# Buck_5V_line_07.net
KiCad netlist of a schematic drawn in Altium Designer
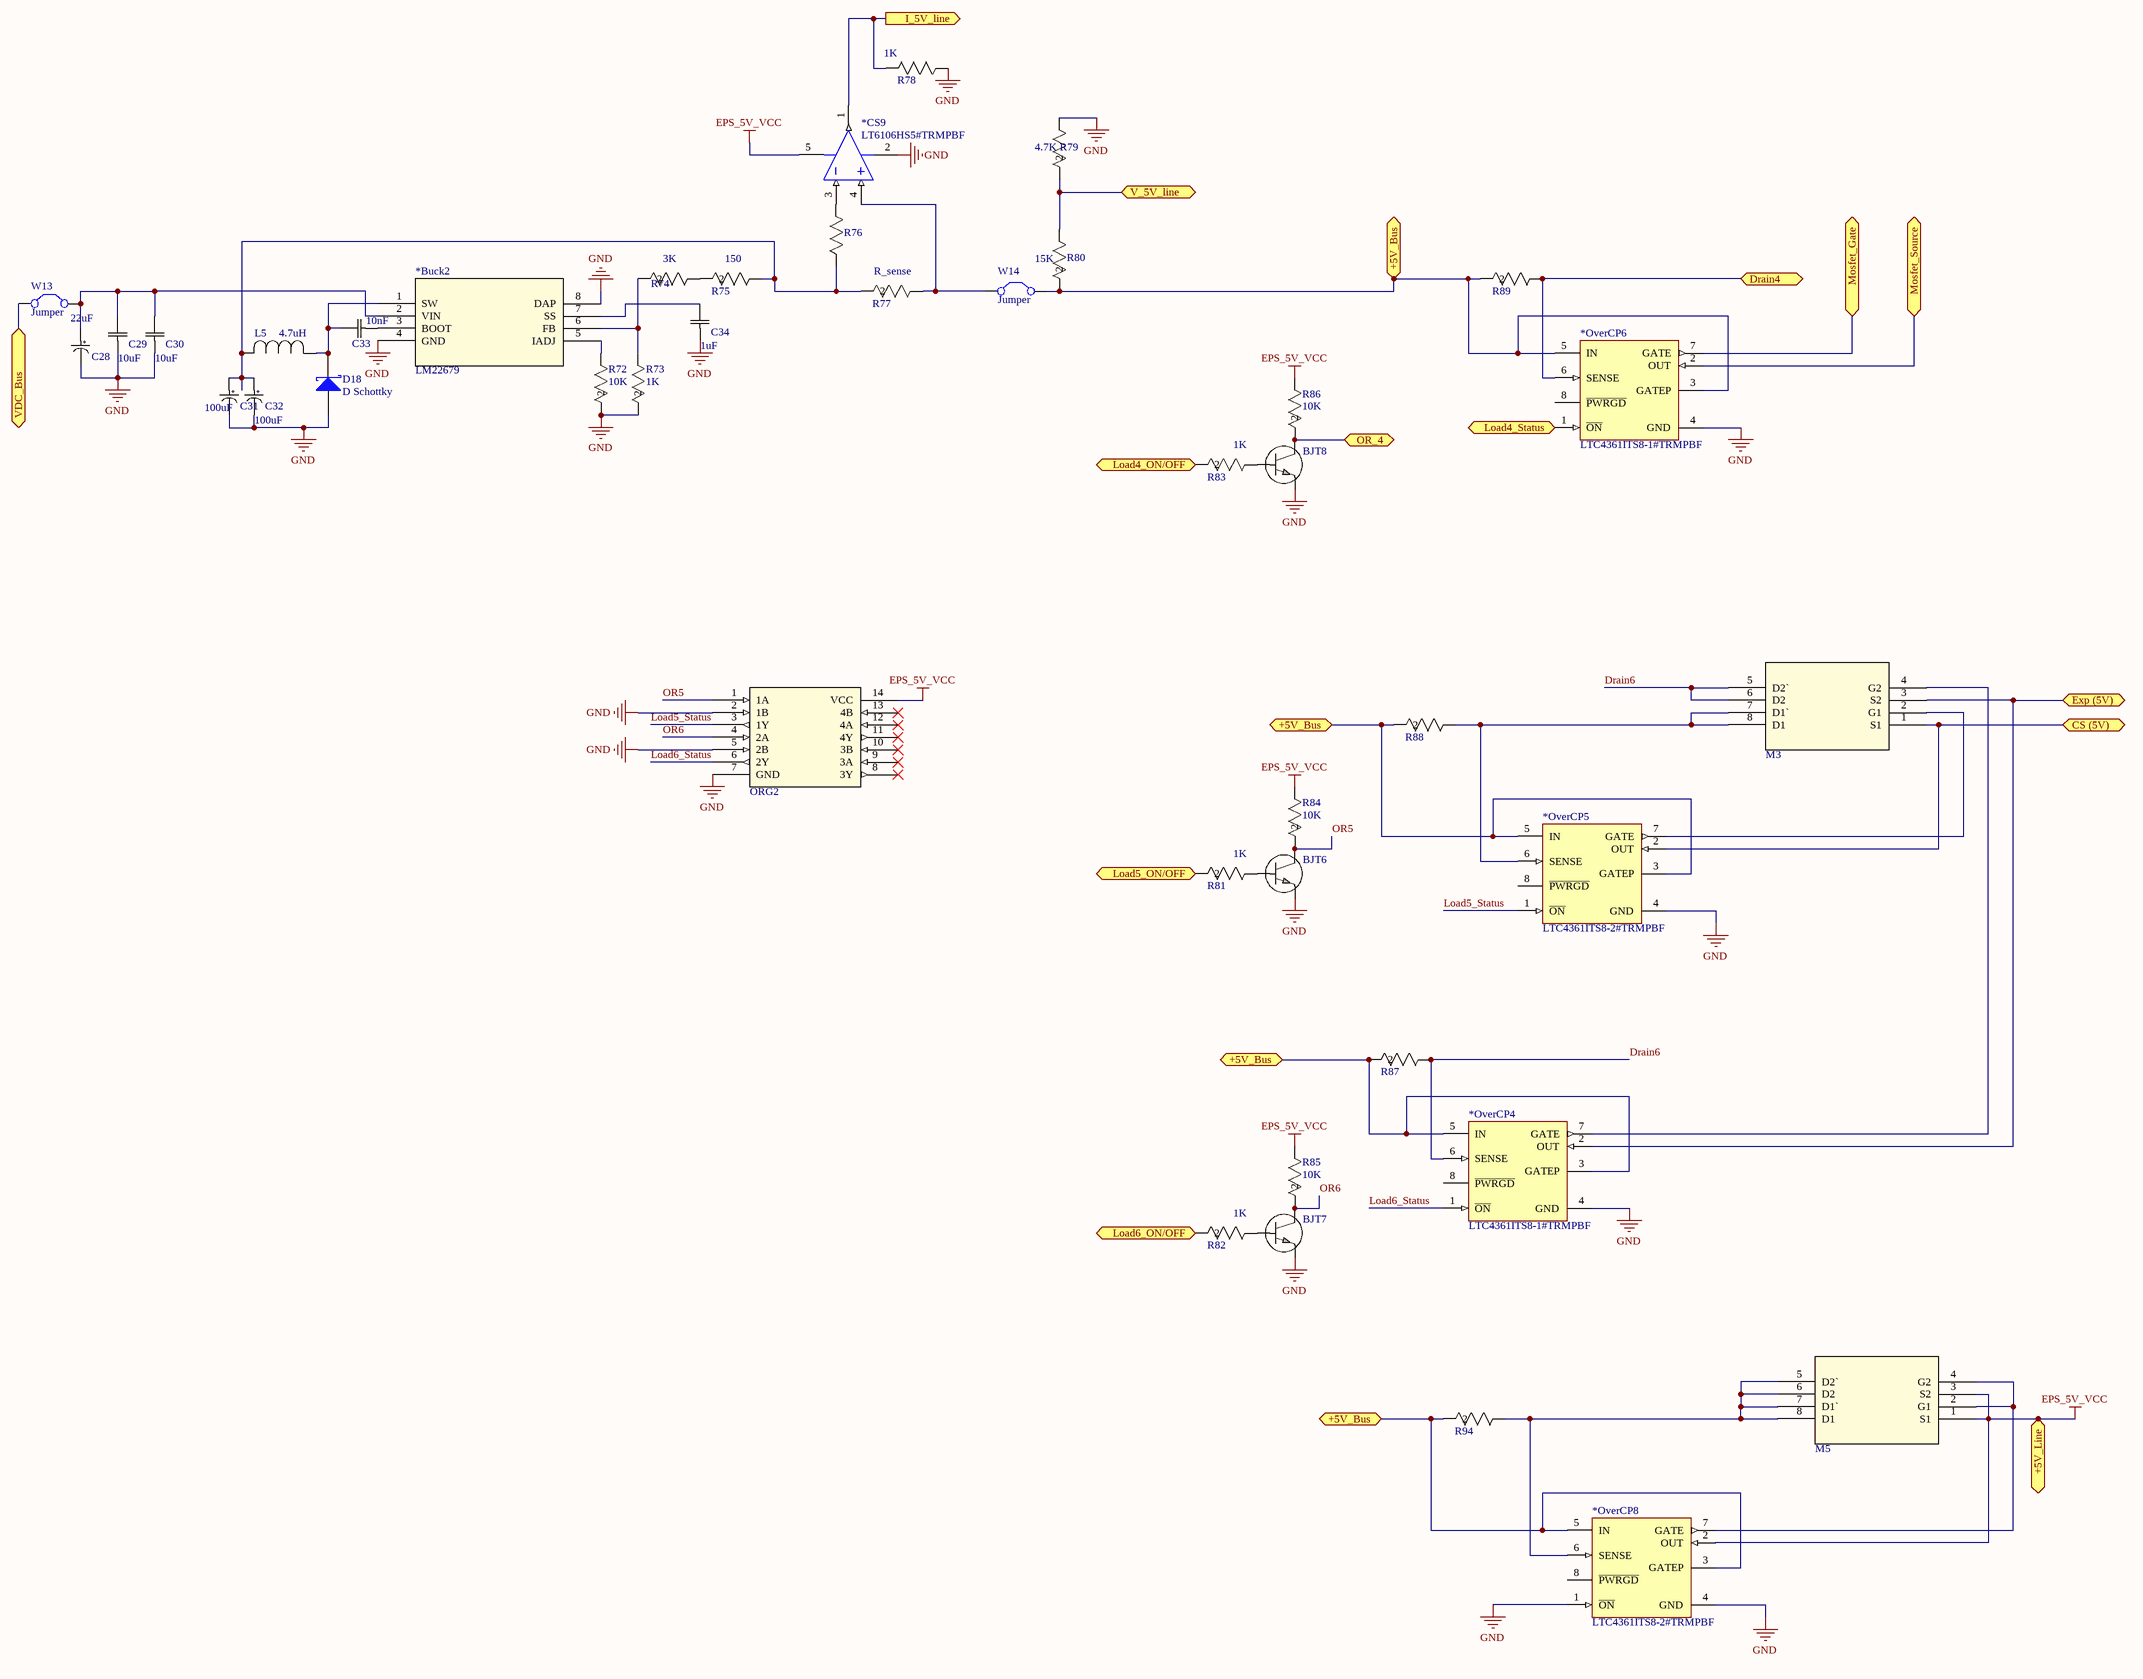
[diagram p0: Buck_5V_line_07.SchDoc]

(export (version "E")
  (design (tool "Eeschema 10.0.6"))
  (components
    (comp (ref "*Buck2")
      (value "LM22679")
      (footprint "TJ7A-M")
      (description "step down converter")
      (fields
        (field (name "MANUFACTURER_PART_NUMBER") "lm22679tj-adjnopb")
        (field (name "COPYRIGHT") "Copyright (C) 2015 Accelerated Designs. All rights reserved")
      )
      (libsource (lib "EPS_lib") (part "LM22679"))
    )
    (comp (ref "*CS9")
      (value "LT6106HS5#TRMPBF")
      (footprint "LT-S5-5-TSOT-23_N")
      (fields
        (field (name "LINEAR TECHNOLOGY PART NUMBER") "LT6106")
        (field (name "MANUFACTURER") "Linear Technology")
      )
      (libsource (lib "Linear Technology Operational Amplifiers (LT2000-LT6000)") (part "LT6106HS5#TRMPBF"))
    )
    (comp (ref "*OverCP4")
      (value "LTC4361ITS8-1#TRMPBF")
      (footprint "LT-TS8-8-TSOT-23_V")
      (fields (field (name "MANUFACTURER") "Linear Technology"))
      (libsource (lib "trial05") (part "LTC4361ITS8-1#TRMPBF"))
    )
    (comp (ref "*OverCP5")
      (value "LTC4361ITS8-2#TRMPBF")
      (footprint "LT-TS8-8-TSOT-23_V")
      (fields
        (field (name "MANUFACTURER") "Linear Technology")
        (field (name "PARTNUMBER") "LTC4361ITS8-1#TRMPBF")
      )
      (libsource (lib "trial05") (part "LTC4361ITS8-1#TRMPBF"))
    )
    (comp (ref "*OverCP6")
      (value "LTC4361ITS8-1#TRMPBF")
      (footprint "LT-TS8-8-TSOT-23_V")
      (fields (field (name "MANUFACTURER") "Linear Technology"))
      (libsource (lib "trial05") (part "LTC4361ITS8-1#TRMPBF"))
    )
    (comp (ref "*OverCP8")
      (value "LTC4361ITS8-2#TRMPBF")
      (footprint "LT-TS8-8-TSOT-23_V")
      (fields
        (field (name "MANUFACTURER") "Linear Technology")
        (field (name "PARTNUMBER") "LTC4361ITS8-1#TRMPBF")
      )
      (libsource (lib "trial05") (part "LTC4361ITS8-1#TRMPBF"))
    )
    (comp (ref "BJT6")
      (value "MMBT2222A")
      (footprint "SOT-23A_L")
      (description "BJT")
      (fields
        (field (name "MANUFACTURER_PART_NUMBER") "2STF1360")
        (field (name "DIGIKEYPARTNUMBER") "497-5211-2-ND")
        (field (name "COPYRIGHT") "Copyright (C) 2015 Accelerated Designs. All rights reserved")
      )
      (libsource (lib "PCDU_Library") (part "2STF1360"))
    )
    (comp (ref "BJT7")
      (value "MMBT2222A")
      (footprint "SOT-23A_L")
      (description "BJT")
      (fields
        (field (name "MANUFACTURER_PART_NUMBER") "2STF1360")
        (field (name "DIGIKEYPARTNUMBER") "497-5211-2-ND")
        (field (name "COPYRIGHT") "Copyright (C) 2015 Accelerated Designs. All rights reserved")
      )
      (libsource (lib "PCDU_Library") (part "2STF1360"))
    )
    (comp (ref "BJT8")
      (value "MMBT2222A")
      (footprint "SOT-23A_L")
      (description "BJT")
      (fields
        (field (name "MANUFACTURER_PART_NUMBER") "2STF1360")
        (field (name "DIGIKEYPARTNUMBER") "497-5211-2-ND")
        (field (name "COPYRIGHT") "Copyright (C) 2015 Accelerated Designs. All rights reserved")
      )
      (libsource (lib "PCDU_Library") (part "2STF1360"))
    )
    (comp (ref "C28")
      (value "22uF")
      (footprint "TAJB")
      (description "Tantalum Capacitor, 22uF")
      (fields
        (field (name "MANUFACTURER_PART_NUMBER") "TAJB226M010RNJ")
        (field (name "COPYRIGHT") "Copyright (C) 2015 Accelerated Designs. All rights reserved")
      )
      (libsource (lib "PCDU_Library") (part "TAJB226M010RNJ"))
    )
    (comp (ref "C29")
      (value "10uF")
      (footprint "PcbLib1:RC0805N")
      (description "Ceramic Capacitor 10uF")
      (fields
        (field (name "DIGIKEYPARTNUMBER") "399-4925-2-ND")
        (field (name "MANUFACTURER_PART_NUMBER") "C0805C106K8PACTU")
        (field (name "COPYRIGHT") "Copyright (C) 2015 Accelerated Designs. All rights reserved")
      )
      (libsource (lib "PCDU_Library") (part "C0805C106K8PACTU"))
    )
    (comp (ref "C30")
      (value "10uF")
      (footprint "PcbLib1:RC0805N")
      (description "Ceramic Capacitor 10uF")
      (fields
        (field (name "DIGIKEYPARTNUMBER") "399-4925-2-ND")
        (field (name "MANUFACTURER_PART_NUMBER") "C0805C106K8PACTU")
        (field (name "COPYRIGHT") "Copyright (C) 2015 Accelerated Designs. All rights reserved")
      )
      (libsource (lib "PCDU_Library") (part "C0805C106K8PACTU"))
    )
    (comp (ref "C31")
      (value "100uF")
      (footprint "TAJB")
      (description "Tantalum Capacitor, 100uF")
      (fields
        (field (name "MANUFACTURER_PART_NUMBER") "TAJB226M010RNJ")
        (field (name "COPYRIGHT") "Copyright (C) 2015 Accelerated Designs. All rights reserved")
      )
      (libsource (lib "PCDU_Library") (part "TAJB226M010RNJ"))
    )
    (comp (ref "C32")
      (value "100uF")
      (footprint "TAJB")
      (description "Tantalum Capacitor,100uF")
      (fields
        (field (name "MANUFACTURER_PART_NUMBER") "TAJB226M010RNJ")
        (field (name "COPYRIGHT") "Copyright (C) 2015 Accelerated Designs. All rights reserved")
      )
      (libsource (lib "PCDU_Library") (part "TAJB226M010RNJ"))
    )
    (comp (ref "C33")
      (value "10nF")
      (footprint "RC0805N")
      (description "Ceramic Capacitor 10nF")
      (fields
        (field (name "MANUFACTURER_PART_NUMBER") "GRM155R71H103KA88D")
        (field (name "COPYRIGHT") "Copyright (C) 2015 Accelerated Designs. All rights reserved")
      )
      (libsource (lib "PCDU_Library") (part "GRM155R71H103KA8"))
    )
    (comp (ref "C34")
      (value "1uF")
      (footprint "PcbLib1:RC0805N")
      (description "Ceramic Capacitor 1uF")
      (fields
        (field (name "MANUFACTURER_PART_NUMBER") "GRM188R61C105KA93D")
        (field (name "COPYRIGHT") "Copyright (C) 2015 Accelerated Designs. All rights reserved")
      )
      (libsource (lib "PCDU_Library") (part "GRM188R61C105KA9"))
    )
    (comp (ref "D18")
      (value "D Schottky")
      (footprint "SMB")
      (description "Schottky Diode, 1A")
      (fields (field (name "PUBLISHER") "Altium Limited"))
      (libsource (lib "PCDU_Library") (part "D Schottky"))
    )
    (comp (ref "L5")
      (value "4.7uH")
      (footprint "IND_SPM6530")
      (description "Inductor, 4.7uH")
      (fields
        (field (name "MANUFACTURER_PART_NUMBER") "SPM6530T-4R7M")
        (field (name "COPYRIGHT") "Copyright (C) 2015 Accelerated Designs. All rights reserved")
      )
      (libsource (lib "PCDU_Library") (part "SPM6530T-4R7M"))
    )
    (comp (ref "M3")
      (value "IRF7329TRPBF")
      (footprint "SO8_L")
      (description "P-MOSFET, DUAL PCh -12V 9.2A")
      (fields
        (field (name "MANUFACTURER") "Infineon / IR")
        (field (name "MOUSER PART NO") "942-IRF7329TRPBF")
      )
      (libsource (lib "PCDU_Library") (part "IRF7329TRPBF"))
    )
    (comp (ref "M5")
      (value "IRF7329TRPBF")
      (footprint "SO8_L")
      (description "P-MOSFET, DUAL PCh -12V 9.2A")
      (fields
        (field (name "MANUFACTURER") "Infineon / IR")
        (field (name "MOUSER PART NO") "942-IRF7329TRPBF")
      )
      (libsource (lib "PCDU_Library") (part "IRF7329TRPBF"))
    )
    (comp (ref "ORG2")
      (value "SN74LV32ADR")
      (footprint "D14-M")
      (description "OR GATE, 4 Channels")
      (fields
        (field (name "MANUFACTURER") "Texas Instruments")
        (field (name "GENERIC_PART_NUMBER") "SN74LV32A")
        (field (name "COPYRIGHT") "Copyright (C) 2015 Accelerated Designs. All rights reserved")
      )
      (libsource (lib "EPS_lib") (part "SN74LV32ADR"))
    )
    (comp (ref "R72")
      (value "10K")
      (footprint "RC0805N")
      (description "Thick Film Resistors, 10k ohm")
      (fields
        (field (name "DIGIKEYPARTNUMBER") "311-4.70KCRTR-ND")
        (field (name "MANUFACTURER_PART_NUMBER") "RC0805FR-074K7L")
        (field (name "COPYRIGHT") "Copyright (C) 2015 Accelerated Designs. All rights reserved")
      )
      (libsource (lib "PCDU_Library") (part "RC0805FR"))
    )
    (comp (ref "R73")
      (value "1K")
      (footprint "RC0805N")
      (description "Thick Film Resistors, 1k ohm")
      (fields
        (field (name "DIGIKEYPARTNUMBER") "311-4.70KCRTR-ND")
        (field (name "MANUFACTURER_PART_NUMBER") "RC0805FR-074K7L")
        (field (name "COPYRIGHT") "Copyright (C) 2015 Accelerated Designs. All rights reserved")
      )
      (libsource (lib "PCDU_Library") (part "RC0805FR"))
    )
    (comp (ref "R74")
      (value "3K")
      (footprint "RC0805N")
      (description "Thick Film Resistors, 3k ohm")
      (fields
        (field (name "DIGIKEYPARTNUMBER") "311-4.70KCRTR-ND")
        (field (name "MANUFACTURER_PART_NUMBER") "RC0805FR-074K7L")
        (field (name "COPYRIGHT") "Copyright (C) 2015 Accelerated Designs. All rights reserved")
      )
      (libsource (lib "PCDU_Library") (part "RC0805FR"))
    )
    (comp (ref "R75")
      (value "150")
      (footprint "RC0805N")
      (description "Thick Film Resistors, 150 ohm")
      (fields
        (field (name "DIGIKEYPARTNUMBER") "311-4.70KCRTR-ND")
        (field (name "MANUFACTURER_PART_NUMBER") "RC0805FR-074K7L")
        (field (name "COPYRIGHT") "Copyright (C) 2015 Accelerated Designs. All rights reserved")
      )
      (libsource (lib "PCDU_Library") (part "RC0805FR"))
    )
    (comp (ref "R76")
      (value "1K")
      (footprint "RC0805N")
      (description "Thick Film Resistors 0805")
      (fields
        (field (name "DIGIKEYPARTNUMBER") "311-4.70KCRTR-ND")
        (field (name "MANUFACTURER_PART_NUMBER") "RC0805FR-074K7L")
        (field (name "COPYRIGHT") "Copyright (C) 2015 Accelerated Designs. All rights reserved")
      )
      (libsource (lib "Schlib1") (part "RC0805FR"))
    )
    (comp (ref "R77")
      (value "R_sense")
      (footprint "RC0805N")
      (description "Sense Resistor 100m ohm 0805")
      (fields
        (field (name "DIGIKEYPARTNUMBER") "311-.10STR-ND")
        (field (name "MANUFACTURER_PART_NUMBER") "RL0805FR-070R1L")
        (field (name "COPYRIGHT") "Copyright (C) 2015 Accelerated Designs. All rights reserved")
      )
      (libsource (lib "Schlib1") (part "RL0805FR-070R1L"))
    )
    (comp (ref "R78")
      (value "1K")
      (footprint "RC0805N")
      (description "Thick Film Resistors 0805")
      (fields
        (field (name "DIGIKEYPARTNUMBER") "311-4.70KCRTR-ND")
        (field (name "MANUFACTURER_PART_NUMBER") "RC0805FR-074K7L")
        (field (name "COPYRIGHT") "Copyright (C) 2015 Accelerated Designs. All rights reserved")
      )
      (libsource (lib "Schlib1") (part "RC0805FR"))
    )
    (comp (ref "R79")
      (value "4.7K")
      (footprint "RC0805N")
      (description "Resistors 0805, 4.7k ohm")
      (fields
        (field (name "DIGIKEYPARTNUMBER") "311-4.70KCRTR-ND")
        (field (name "MANUFACTURER_PART_NUMBER") "RC0805FR-074K7L")
        (field (name "COPYRIGHT") "Copyright (C) 2015 Accelerated Designs. All rights reserved")
      )
      (libsource (lib "PCDU_Library") (part "RC0805FR"))
    )
    (comp (ref "R80")
      (value "15K")
      (footprint "RC0805N")
      (description "Resistors 0805, 15k ohm")
      (fields
        (field (name "DIGIKEYPARTNUMBER") "311-4.70KCRTR-ND")
        (field (name "MANUFACTURER_PART_NUMBER") "RC0805FR-074K7L")
        (field (name "COPYRIGHT") "Copyright (C) 2015 Accelerated Designs. All rights reserved")
      )
      (libsource (lib "PCDU_Library") (part "RC0805FR"))
    )
    (comp (ref "R81")
      (value "1K")
      (footprint "RC0805N")
      (description "Thick Film Resistors, 1k ohm")
      (fields
        (field (name "DIGIKEYPARTNUMBER") "311-4.70KCRTR-ND")
        (field (name "MANUFACTURER_PART_NUMBER") "RC0805FR-074K7L")
        (field (name "COPYRIGHT") "Copyright (C) 2015 Accelerated Designs. All rights reserved")
      )
      (libsource (lib "PCDU_Library") (part "RC0805FR"))
    )
    (comp (ref "R82")
      (value "1K")
      (footprint "RC0805N")
      (description "Thick Film Resistors, 1k ohm")
      (fields
        (field (name "DIGIKEYPARTNUMBER") "311-4.70KCRTR-ND")
        (field (name "MANUFACTURER_PART_NUMBER") "RC0805FR-074K7L")
        (field (name "COPYRIGHT") "Copyright (C) 2015 Accelerated Designs. All rights reserved")
      )
      (libsource (lib "PCDU_Library") (part "RC0805FR"))
    )
    (comp (ref "R83")
      (value "1K")
      (footprint "RC0805N")
      (description "Thick Film Resistors, 1k ohm")
      (fields
        (field (name "DIGIKEYPARTNUMBER") "311-4.70KCRTR-ND")
        (field (name "MANUFACTURER_PART_NUMBER") "RC0805FR-074K7L")
        (field (name "COPYRIGHT") "Copyright (C) 2015 Accelerated Designs. All rights reserved")
      )
      (libsource (lib "PCDU_Library") (part "RC0805FR"))
    )
    (comp (ref "R84")
      (value "10K")
      (footprint "PcbLib1:RC0805N")
      (description "Thick Film Resistors, 10k ohm")
      (fields
        (field (name "DIGIKEYPARTNUMBER") "311-4.70KCRTR-ND")
        (field (name "MANUFACTURER_PART_NUMBER") "RC0805FR-074K7L")
        (field (name "COPYRIGHT") "Copyright (C) 2015 Accelerated Designs. All rights reserved")
      )
      (libsource (lib "PCDU_Library") (part "RC0805FR"))
    )
    (comp (ref "R85")
      (value "10K")
      (footprint "PcbLib1:RC0805N")
      (description "Thick Film Resistors, 10k ohm")
      (fields
        (field (name "DIGIKEYPARTNUMBER") "311-4.70KCRTR-ND")
        (field (name "MANUFACTURER_PART_NUMBER") "RC0805FR-074K7L")
        (field (name "COPYRIGHT") "Copyright (C) 2015 Accelerated Designs. All rights reserved")
      )
      (libsource (lib "PCDU_Library") (part "RC0805FR"))
    )
    (comp (ref "R86")
      (value "10K")
      (footprint "PcbLib1:RC0805N")
      (description "Thick Film Resistors, 10k ohm")
      (fields
        (field (name "DIGIKEYPARTNUMBER") "311-4.70KCRTR-ND")
        (field (name "MANUFACTURER_PART_NUMBER") "RC0805FR-074K7L")
        (field (name "COPYRIGHT") "Copyright (C) 2015 Accelerated Designs. All rights reserved")
      )
      (libsource (lib "PCDU_Library") (part "RC0805FR"))
    )
    (comp (ref "R87")
      (value "RL0805FR-070R1L")
      (footprint "RC0805N")
      (description "Sense Resistor 100m ohm 0805")
      (fields
        (field (name "DIGIKEYPARTNUMBER") "311-.10STR-ND")
        (field (name "TOLERANCE") "Â±1%")
        (field (name "COPYRIGHT") "Copyright (C) 2015 Accelerated Designs. All rights reserved")
      )
      (libsource (lib "Schlib1") (part "RL0805FR-070R1L"))
    )
    (comp (ref "R88")
      (value "RL0805FR-070R1L")
      (footprint "RC0805N")
      (description "Sense Resistor 100m ohm 0805")
      (fields
        (field (name "DIGIKEYPARTNUMBER") "311-.10STR-ND")
        (field (name "TOLERANCE") "Â±1%")
        (field (name "COPYRIGHT") "Copyright (C) 2015 Accelerated Designs. All rights reserved")
      )
      (libsource (lib "Schlib1") (part "RL0805FR-070R1L"))
    )
    (comp (ref "R89")
      (value "RL0805FR-070R1L")
      (footprint "RC0805N")
      (description "Sense Resistor 100m ohm 0805")
      (fields
        (field (name "DIGIKEYPARTNUMBER") "311-.10STR-ND")
        (field (name "TOLERANCE") "Â±1%")
        (field (name "COPYRIGHT") "Copyright (C) 2015 Accelerated Designs. All rights reserved")
      )
      (libsource (lib "Schlib1") (part "RL0805FR-070R1L"))
    )
    (comp (ref "R94")
      (value "RL0805FR-070R1L")
      (footprint "RC0805N")
      (description "Sense Resistor 100m ohm 0805")
      (fields
        (field (name "DIGIKEYPARTNUMBER") "311-.10STR-ND")
        (field (name "TOLERANCE") "Â±1%")
        (field (name "COPYRIGHT") "Copyright (C) 2015 Accelerated Designs. All rights reserved")
      )
      (libsource (lib "Schlib1") (part "RL0805FR-070R1L"))
    )
    (comp (ref "W13")
      (value "Jumper")
      (footprint "PcbLib1:RAD-0.1")
      (description "Jumper Wire")
      (fields (field (name "PUBLISHER") "Altium Limited"))
      (libsource (lib "EPS_lib") (part "Jumper"))
    )
    (comp (ref "W14")
      (value "Jumper")
      (footprint "PcbLib1:RAD-0.1")
      (description "Jumper Wire")
      (fields (field (name "PUBLISHER") "Altium Limited"))
      (libsource (lib "Miscellaneous Devices") (part "Jumper"))
    )
  )
  (nets
    (net (code "1") (name "/+5V_Bus") (class "Default")
      (node (ref "*OverCP4") (pin "3") (pinfunction "GATEP_3") (pintype "passive"))
      (node (ref "*OverCP4") (pin "5") (pinfunction "IN_5") (pintype "power_in"))
      (node (ref "*OverCP5") (pin "3") (pinfunction "GATEP_3") (pintype "passive"))
      (node (ref "*OverCP5") (pin "5") (pinfunction "IN_5") (pintype "power_in"))
      (node (ref "*OverCP6") (pin "3") (pinfunction "GATEP_3") (pintype "passive"))
      (node (ref "*OverCP6") (pin "5") (pinfunction "IN_5") (pintype "power_in"))
      (node (ref "*OverCP8") (pin "3") (pinfunction "GATEP_3") (pintype "passive"))
      (node (ref "*OverCP8") (pin "5") (pinfunction "IN_5") (pintype "power_in"))
      (node (ref "R80") (pin "2") (pinfunction "2_2") (pintype "passive"))
      (node (ref "R87") (pin "2") (pinfunction "2_2") (pintype "passive"))
      (node (ref "R88") (pin "2") (pinfunction "2_2") (pintype "passive"))
      (node (ref "R89") (pin "2") (pinfunction "2_2") (pintype "passive"))
      (node (ref "R94") (pin "2") (pinfunction "2_2") (pintype "passive"))
      (node (ref "W14") (pin "2") (pinfunction "C2_2") (pintype "passive"))
    )
    (net (code "2") (name "/CS (5V)") (class "Default")
      (node (ref "*OverCP5") (pin "2") (pinfunction "OUT_2") (pintype "input"))
      (node (ref "M3") (pin "1") (pinfunction "S1_1") (pintype "passive"))
    )
    (net (code "3") (name "/Drain4") (class "Default")
      (node (ref "*OverCP6") (pin "6") (pinfunction "SENSE_6") (pintype "input"))
      (node (ref "R89") (pin "1") (pinfunction "1_1") (pintype "passive"))
    )
    (net (code "4") (name "/Drain6") (class "Default")
      (node (ref "*OverCP4") (pin "6") (pinfunction "SENSE_6") (pintype "input"))
      (node (ref "M3") (pin "5") (pinfunction "D2`_5") (pintype "passive"))
      (node (ref "M3") (pin "6") (pinfunction "D2_6") (pintype "passive"))
      (node (ref "R87") (pin "1") (pinfunction "1_1") (pintype "passive"))
    )
    (net (code "5") (name "/Exp (5V)") (class "Default")
      (node (ref "*OverCP4") (pin "2") (pinfunction "OUT_2") (pintype "input"))
      (node (ref "M3") (pin "3") (pinfunction "S2_3") (pintype "passive"))
    )
    (net (code "6") (name "/I_5V_line") (class "Default")
      (node (ref "*CS9") (pin "1") (pinfunction "OUT_1") (pintype "output"))
      (node (ref "R78") (pin "1") (pinfunction "1_1") (pintype "passive"))
    )
    (net (code "7") (name "/Load4_ON{slash}OFF") (class "Default")
      (node (ref "R83") (pin "2") (pinfunction "2_2") (pintype "passive"))
    )
    (net (code "8") (name "/Load4_Status") (class "Default")
      (node (ref "*OverCP6") (pin "1") (pinfunction "~{ON}_1") (pintype "input"))
    )
    (net (code "9") (name "/Load5_ON{slash}OFF") (class "Default")
      (node (ref "R81") (pin "2") (pinfunction "2_2") (pintype "passive"))
    )
    (net (code "10") (name "/Load5_Status") (class "Default")
      (node (ref "*OverCP5") (pin "1") (pinfunction "~{ON}_1") (pintype "input"))
      (node (ref "ORG2") (pin "3") (pinfunction "1Y_3") (pintype "output"))
    )
    (net (code "11") (name "/Load6_ON{slash}OFF") (class "Default")
      (node (ref "R82") (pin "2") (pinfunction "2_2") (pintype "passive"))
    )
    (net (code "12") (name "/Load6_Status") (class "Default")
      (node (ref "*OverCP4") (pin "1") (pinfunction "~{ON}_1") (pintype "input"))
      (node (ref "ORG2") (pin "6") (pinfunction "2Y_6") (pintype "output"))
    )
    (net (code "13") (name "/Mosfet_Gate") (class "Default")
      (node (ref "*OverCP6") (pin "7") (pinfunction "GATE_7") (pintype "output"))
    )
    (net (code "14") (name "/Mosfet_Source") (class "Default")
      (node (ref "*OverCP6") (pin "2") (pinfunction "OUT_2") (pintype "input"))
    )
    (net (code "15") (name "/OR5") (class "Default")
      (node (ref "BJT6") (pin "2") (pinfunction "C_2") (pintype "passive"))
      (node (ref "ORG2") (pin "1") (pinfunction "1A_1") (pintype "input"))
      (node (ref "R84") (pin "2") (pinfunction "2_2") (pintype "passive"))
    )
    (net (code "16") (name "/OR6") (class "Default")
      (node (ref "BJT7") (pin "2") (pinfunction "C_2") (pintype "passive"))
      (node (ref "ORG2") (pin "4") (pinfunction "2A_4") (pintype "input"))
      (node (ref "R85") (pin "2") (pinfunction "2_2") (pintype "passive"))
    )
    (net (code "17") (name "/OR_4") (class "Default")
      (node (ref "BJT8") (pin "2") (pinfunction "C_2") (pintype "passive"))
      (node (ref "R86") (pin "2") (pinfunction "2_2") (pintype "passive"))
    )
    (net (code "18") (name "/VDC_Bus") (class "Default")
      (node (ref "W13") (pin "1") (pinfunction "C1_1") (pintype "passive"))
    )
    (net (code "19") (name "/V_5V_line") (class "Default")
      (node (ref "R79") (pin "2") (pinfunction "2_2") (pintype "passive"))
      (node (ref "R80") (pin "1") (pinfunction "1_1") (pintype "passive"))
    )
    (net (code "20") (name "EPS_5V_VCC") (class "Default")
      (node (ref "*CS9") (pin "5") (pinfunction "V+_5") (pintype "power_in"))
      (node (ref "*OverCP8") (pin "2") (pinfunction "OUT_2") (pintype "input"))
      (node (ref "M5") (pin "1") (pinfunction "S1_1") (pintype "passive"))
      (node (ref "M5") (pin "3") (pinfunction "S2_3") (pintype "passive"))
      (node (ref "ORG2") (pin "14") (pinfunction "VCC_14") (pintype "passive"))
      (node (ref "R84") (pin "1") (pinfunction "1_1") (pintype "passive"))
      (node (ref "R85") (pin "1") (pinfunction "1_1") (pintype "passive"))
      (node (ref "R86") (pin "1") (pinfunction "1_1") (pintype "passive"))
    )
    (net (code "21") (name "GND") (class "Default")
      (node (ref "*Buck2") (pin "4") (pinfunction "GND_4") (pintype "power_in"))
      (node (ref "*Buck2") (pin "8") (pinfunction "DAP_8") (pintype "passive"))
      (node (ref "*CS9") (pin "2") (pinfunction "V-_2") (pintype "power_in"))
      (node (ref "*OverCP4") (pin "4") (pinfunction "GND_4") (pintype "power_in"))
      (node (ref "*OverCP5") (pin "4") (pinfunction "GND_4") (pintype "power_in"))
      (node (ref "*OverCP6") (pin "4") (pinfunction "GND_4") (pintype "power_in"))
      (node (ref "*OverCP8") (pin "1") (pinfunction "~{ON}_1") (pintype "input"))
      (node (ref "*OverCP8") (pin "4") (pinfunction "GND_4") (pintype "power_in"))
      (node (ref "BJT6") (pin "3") (pinfunction "E_3") (pintype "passive"))
      (node (ref "BJT7") (pin "3") (pinfunction "E_3") (pintype "passive"))
      (node (ref "BJT8") (pin "3") (pinfunction "E_3") (pintype "passive"))
      (node (ref "C28") (pin "2") (pinfunction "2_2") (pintype "passive"))
      (node (ref "C29") (pin "1") (pinfunction "1_1") (pintype "passive"))
      (node (ref "C30") (pin "1") (pinfunction "1_1") (pintype "passive"))
      (node (ref "C31") (pin "2") (pinfunction "2_2") (pintype "passive"))
      (node (ref "C32") (pin "2") (pinfunction "2_2") (pintype "passive"))
      (node (ref "C34") (pin "1") (pinfunction "1_1") (pintype "passive"))
      (node (ref "D18") (pin "1") (pinfunction "A_1") (pintype "passive"))
      (node (ref "ORG2") (pin "2") (pinfunction "1B_2") (pintype "input"))
      (node (ref "ORG2") (pin "5") (pinfunction "2B_5") (pintype "input"))
      (node (ref "ORG2") (pin "7") (pinfunction "GND_7") (pintype "power_in"))
      (node (ref "R72") (pin "2") (pinfunction "2_2") (pintype "passive"))
      (node (ref "R73") (pin "2") (pinfunction "2_2") (pintype "passive"))
      (node (ref "R78") (pin "2") (pinfunction "2_2") (pintype "passive"))
      (node (ref "R79") (pin "1") (pinfunction "1_1") (pintype "passive"))
    )
    (net (code "22") (name "Net-(*Buck2-BOOT)") (class "Default")
      (node (ref "*Buck2") (pin "3") (pinfunction "BOOT_3") (pintype "passive"))
      (node (ref "C33") (pin "1") (pinfunction "1_1") (pintype "passive"))
    )
    (net (code "23") (name "Net-(*Buck2-FB)") (class "Default")
      (node (ref "*Buck2") (pin "6") (pinfunction "FB_6") (pintype "passive"))
      (node (ref "R73") (pin "1") (pinfunction "1_1") (pintype "passive"))
      (node (ref "R74") (pin "2") (pinfunction "2_2") (pintype "passive"))
    )
    (net (code "24") (name "Net-(*Buck2-IADJ)") (class "Default")
      (node (ref "*Buck2") (pin "5") (pinfunction "IADJ_5") (pintype "passive"))
      (node (ref "R72") (pin "1") (pinfunction "1_1") (pintype "passive"))
    )
    (net (code "25") (name "Net-(*Buck2-SS)") (class "Default")
      (node (ref "*Buck2") (pin "7") (pinfunction "SS_7") (pintype "passive"))
      (node (ref "C34") (pin "2") (pinfunction "2_2") (pintype "passive"))
    )
    (net (code "26") (name "Net-(*Buck2-SW)") (class "Default")
      (node (ref "*Buck2") (pin "1") (pinfunction "SW_1") (pintype "passive"))
      (node (ref "C33") (pin "2") (pinfunction "2_2") (pintype "passive"))
      (node (ref "D18") (pin "2") (pinfunction "K_2") (pintype "passive"))
      (node (ref "L5") (pin "1") (pinfunction "1_1") (pintype "passive"))
    )
    (net (code "27") (name "Net-(*Buck2-VIN)") (class "Default")
      (node (ref "*Buck2") (pin "2") (pinfunction "VIN_2") (pintype "power_in"))
      (node (ref "C28") (pin "1") (pinfunction "1_1") (pintype "passive"))
      (node (ref "C29") (pin "2") (pinfunction "2_2") (pintype "passive"))
      (node (ref "C30") (pin "2") (pinfunction "2_2") (pintype "passive"))
      (node (ref "W13") (pin "2") (pinfunction "C2_2") (pintype "passive"))
    )
    (net (code "28") (name "Net-(*CS9-+IN)") (class "Default")
      (node (ref "*CS9") (pin "4") (pinfunction "+IN_4") (pintype "input"))
      (node (ref "R77") (pin "1") (pinfunction "1_1") (pintype "passive"))
      (node (ref "W14") (pin "1") (pinfunction "C1_1") (pintype "passive"))
    )
    (net (code "29") (name "Net-(*CS9--IN)") (class "Default")
      (node (ref "*CS9") (pin "3") (pinfunction "-IN_3") (pintype "input"))
      (node (ref "R76") (pin "1") (pinfunction "1_1") (pintype "passive"))
    )
    (net (code "30") (name "Net-(*OverCP4-GATE)") (class "Default")
      (node (ref "*OverCP4") (pin "7") (pinfunction "GATE_7") (pintype "output"))
      (node (ref "M3") (pin "4") (pinfunction "G2_4") (pintype "passive"))
    )
    (net (code "31") (name "Net-(*OverCP5-GATE)") (class "Default")
      (node (ref "*OverCP5") (pin "7") (pinfunction "GATE_7") (pintype "output"))
      (node (ref "M3") (pin "2") (pinfunction "G1_2") (pintype "passive"))
    )
    (net (code "32") (name "Net-(*OverCP5-SENSE)") (class "Default")
      (node (ref "*OverCP5") (pin "6") (pinfunction "SENSE_6") (pintype "input"))
      (node (ref "M3") (pin "7") (pinfunction "D1`_7") (pintype "passive"))
      (node (ref "M3") (pin "8") (pinfunction "D1_8") (pintype "passive"))
      (node (ref "R88") (pin "1") (pinfunction "1_1") (pintype "passive"))
    )
    (net (code "33") (name "Net-(*OverCP8-GATE)") (class "Default")
      (node (ref "*OverCP8") (pin "7") (pinfunction "GATE_7") (pintype "output"))
      (node (ref "M5") (pin "2") (pinfunction "G1_2") (pintype "passive"))
      (node (ref "M5") (pin "4") (pinfunction "G2_4") (pintype "passive"))
    )
    (net (code "34") (name "Net-(*OverCP8-SENSE)") (class "Default")
      (node (ref "*OverCP8") (pin "6") (pinfunction "SENSE_6") (pintype "input"))
      (node (ref "M5") (pin "5") (pinfunction "D2`_5") (pintype "passive"))
      (node (ref "M5") (pin "6") (pinfunction "D2_6") (pintype "passive"))
      (node (ref "M5") (pin "7") (pinfunction "D1`_7") (pintype "passive"))
      (node (ref "M5") (pin "8") (pinfunction "D1_8") (pintype "passive"))
      (node (ref "R94") (pin "1") (pinfunction "1_1") (pintype "passive"))
    )
    (net (code "35") (name "Net-(BJT6-B)") (class "Default")
      (node (ref "BJT6") (pin "1") (pinfunction "B_1") (pintype "passive"))
      (node (ref "R81") (pin "1") (pinfunction "1_1") (pintype "passive"))
    )
    (net (code "36") (name "Net-(BJT7-B)") (class "Default")
      (node (ref "BJT7") (pin "1") (pinfunction "B_1") (pintype "passive"))
      (node (ref "R82") (pin "1") (pinfunction "1_1") (pintype "passive"))
    )
    (net (code "37") (name "Net-(BJT8-B)") (class "Default")
      (node (ref "BJT8") (pin "1") (pinfunction "B_1") (pintype "passive"))
      (node (ref "R83") (pin "1") (pinfunction "1_1") (pintype "passive"))
    )
    (net (code "38") (name "Net-(C31-Pad1)") (class "Default")
      (node (ref "C31") (pin "1") (pinfunction "1_1") (pintype "passive"))
      (node (ref "C32") (pin "1") (pinfunction "1_1") (pintype "passive"))
      (node (ref "L5") (pin "2") (pinfunction "2_2") (pintype "passive"))
      (node (ref "R75") (pin "1") (pinfunction "1_1") (pintype "passive"))
      (node (ref "R76") (pin "2") (pinfunction "2_2") (pintype "passive"))
      (node (ref "R77") (pin "2") (pinfunction "2_2") (pintype "passive"))
    )
    (net (code "39") (name "Net-(R74-Pad1)") (class "Default")
      (node (ref "R74") (pin "1") (pinfunction "1_1") (pintype "passive"))
      (node (ref "R75") (pin "2") (pinfunction "2_2") (pintype "passive"))
    )
    (net (code "40") (name "unconnected-(*OverCP4-~{PWRGD}-Pad8)") (class "Default")
      (node (ref "*OverCP4") (pin "8") (pinfunction "~{PWRGD}_8") (pintype "tri_state"))
    )
    (net (code "41") (name "unconnected-(*OverCP5-~{PWRGD}-Pad8)") (class "Default")
      (node (ref "*OverCP5") (pin "8") (pinfunction "~{PWRGD}_8") (pintype "tri_state"))
    )
    (net (code "42") (name "unconnected-(*OverCP6-~{PWRGD}-Pad8)") (class "Default")
      (node (ref "*OverCP6") (pin "8") (pinfunction "~{PWRGD}_8") (pintype "tri_state"))
    )
    (net (code "43") (name "unconnected-(*OverCP8-~{PWRGD}-Pad8)") (class "Default")
      (node (ref "*OverCP8") (pin "8") (pinfunction "~{PWRGD}_8") (pintype "tri_state"))
    )
    (net (code "44") (name "unconnected-(ORG2-3A-Pad9)") (class "Default")
      (node (ref "ORG2") (pin "9") (pinfunction "3A_9") (pintype "input+no_connect"))
    )
    (net (code "45") (name "unconnected-(ORG2-3B-Pad10)") (class "Default")
      (node (ref "ORG2") (pin "10") (pinfunction "3B_10") (pintype "input+no_connect"))
    )
    (net (code "46") (name "unconnected-(ORG2-3Y-Pad8)") (class "Default")
      (node (ref "ORG2") (pin "8") (pinfunction "3Y_8") (pintype "output+no_connect"))
    )
    (net (code "47") (name "unconnected-(ORG2-4A-Pad12)") (class "Default")
      (node (ref "ORG2") (pin "12") (pinfunction "4A_12") (pintype "input+no_connect"))
    )
    (net (code "48") (name "unconnected-(ORG2-4B-Pad13)") (class "Default")
      (node (ref "ORG2") (pin "13") (pinfunction "4B_13") (pintype "input+no_connect"))
    )
    (net (code "49") (name "unconnected-(ORG2-4Y-Pad11)") (class "Default")
      (node (ref "ORG2") (pin "11") (pinfunction "4Y_11") (pintype "output+no_connect"))
    )
  )
)
